# design1.net
KiCad netlist of a schematic drawn in EAGLE
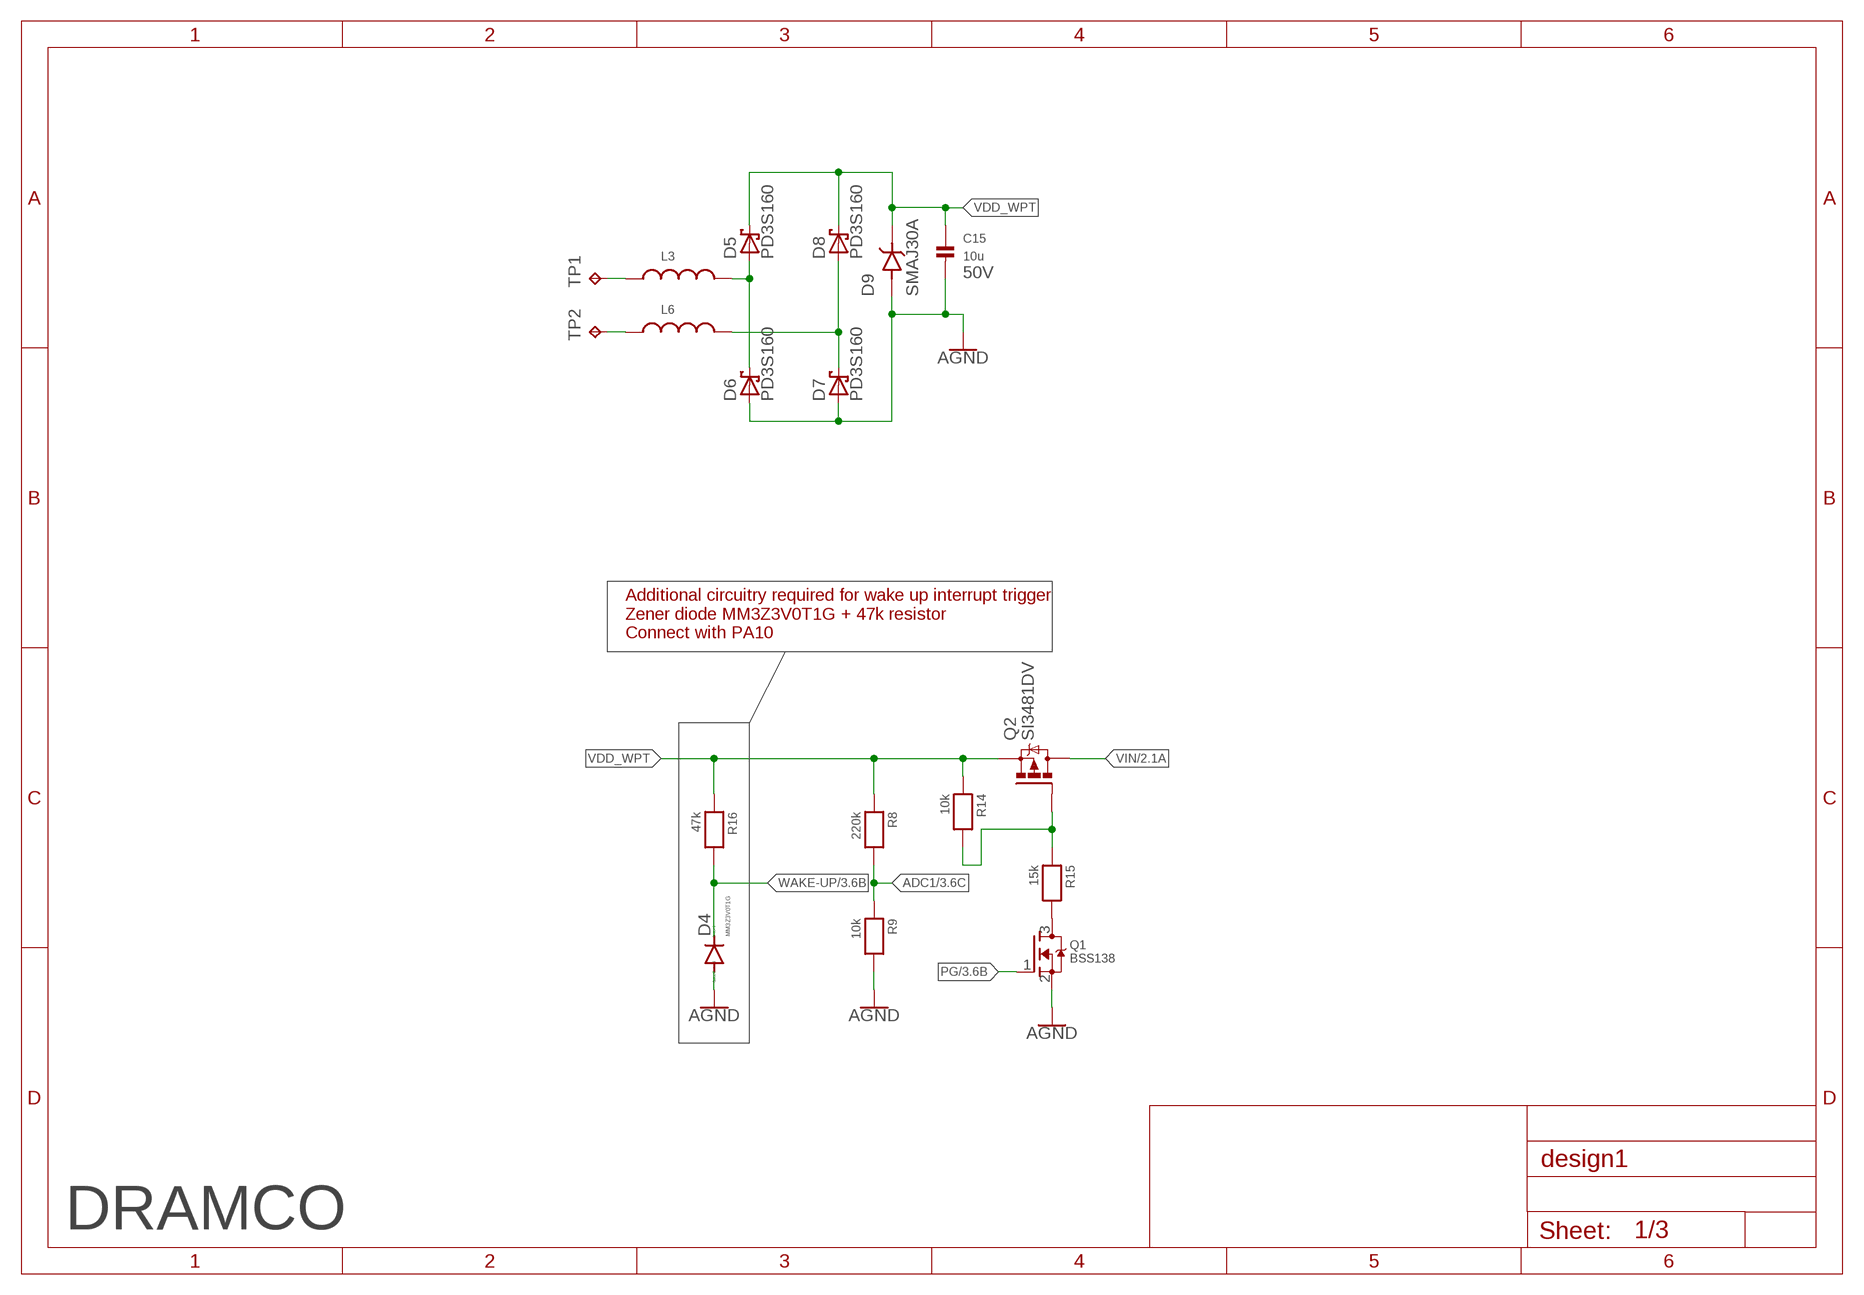
[diagram p0: schematic, sheet 1]
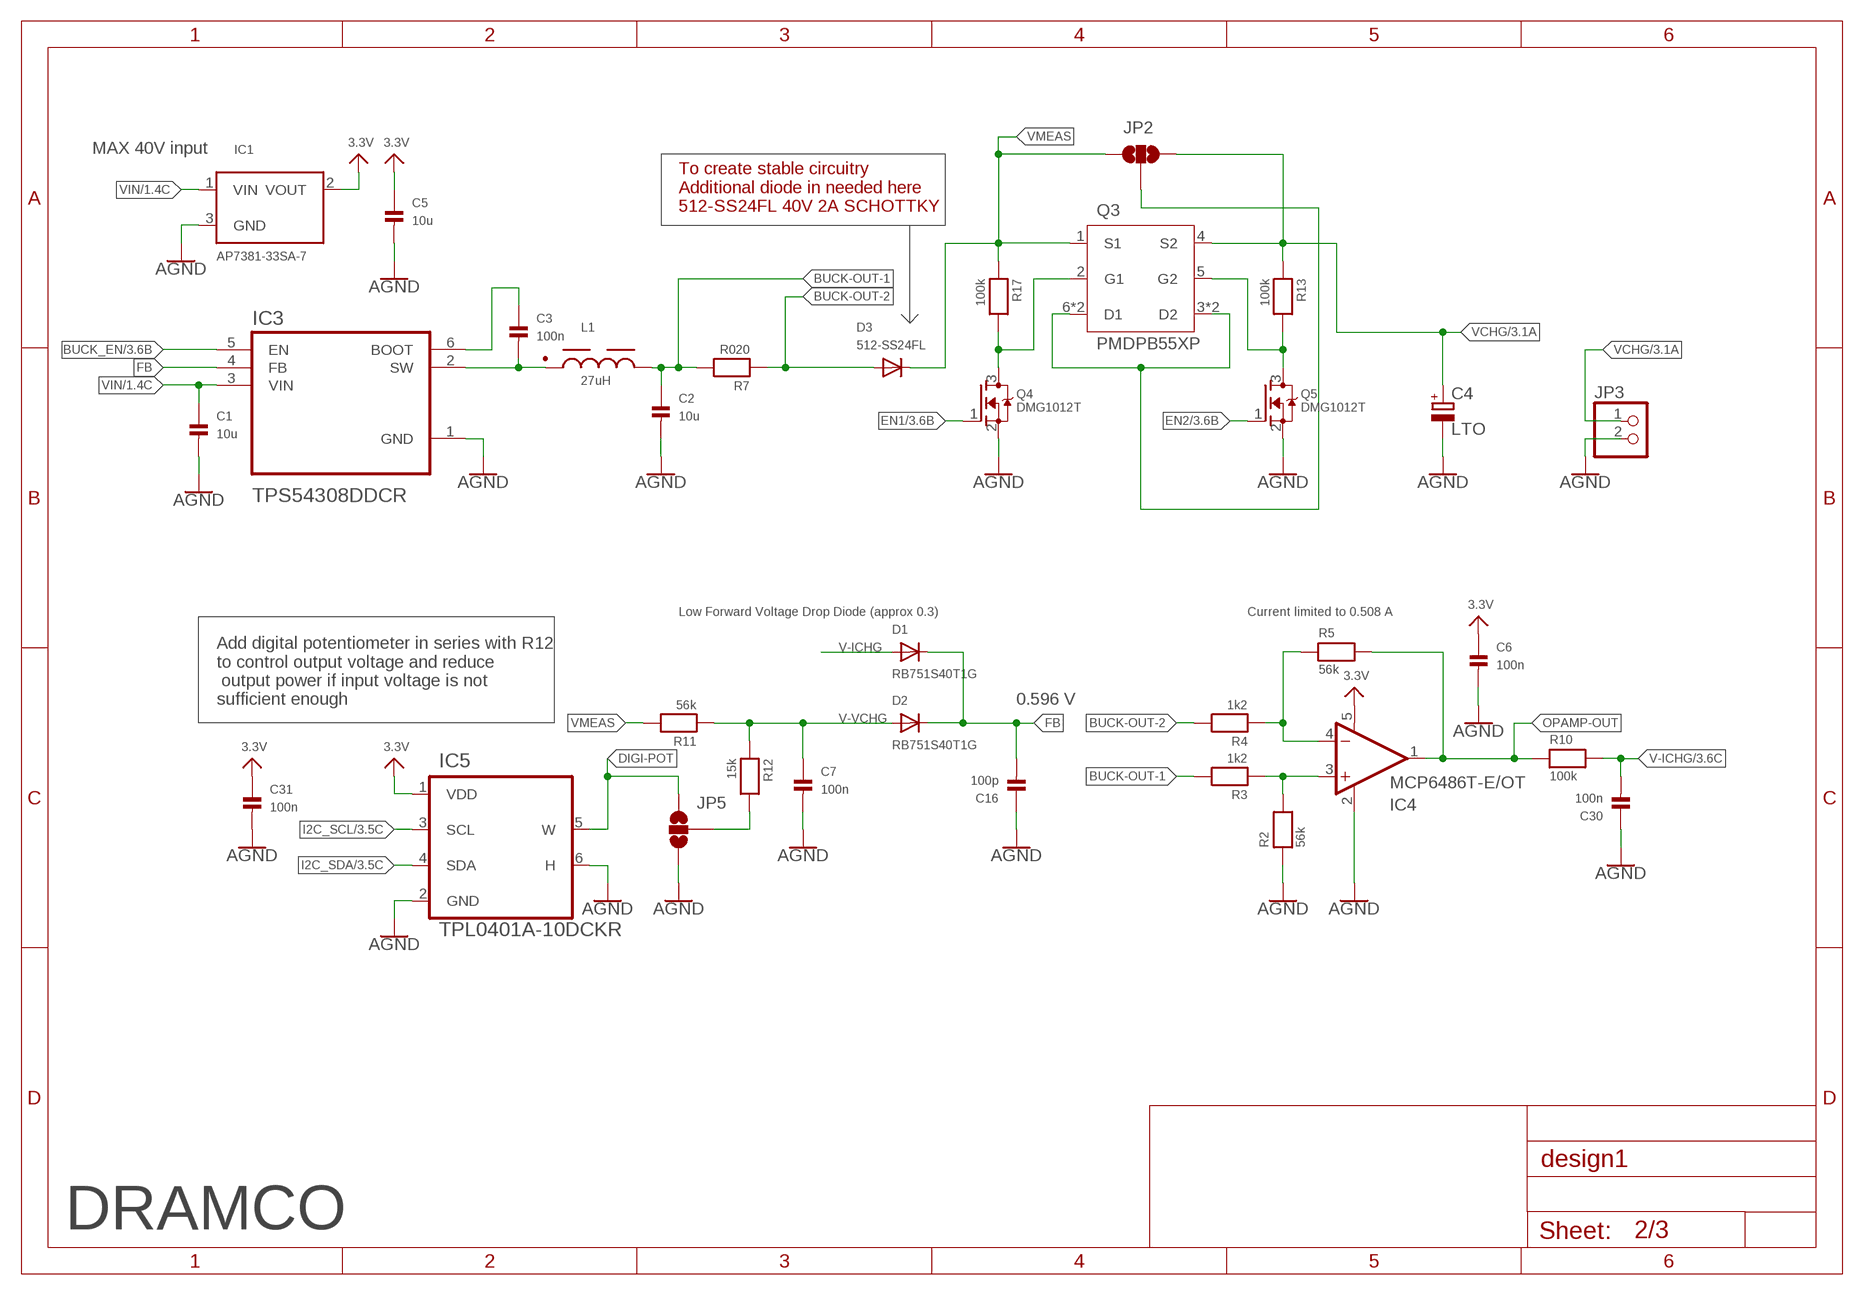
[diagram p1: schematic, sheet 2]
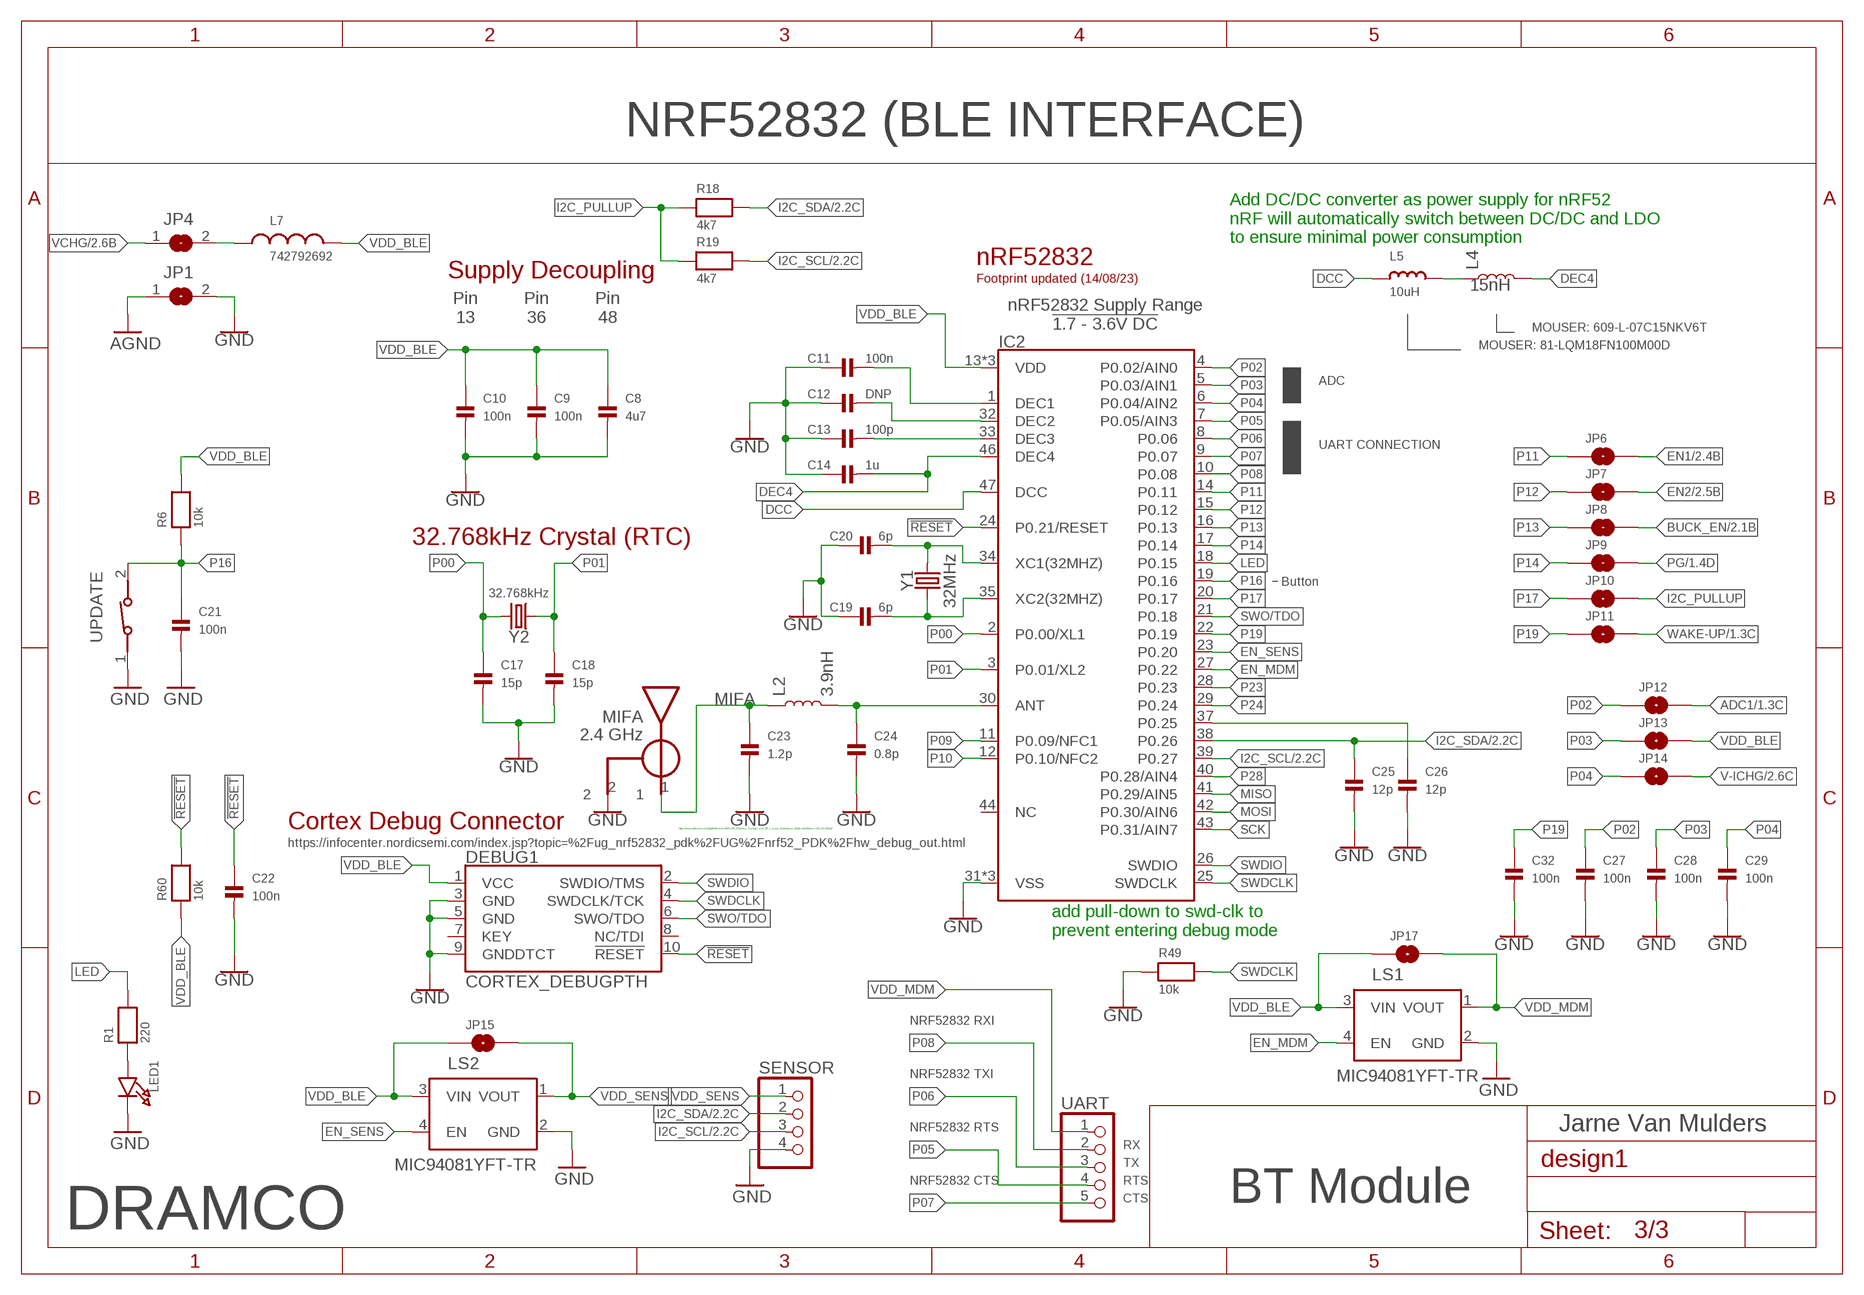
[diagram p2: schematic, sheet 3]

(export (version "E")
  (design (tool "Eeschema 10.0.6"))
  (components
    (comp (ref "C1")
      (value "10u")
      (footprint "eagle-import:0603")
      (libsource (lib "eagle-import") (part "CAP_CERAMIC0603"))
    )
    (comp (ref "C2")
      (value "10u")
      (footprint "eagle-import:0603")
      (libsource (lib "eagle-import") (part "CAP_CERAMIC0603"))
    )
    (comp (ref "C3")
      (value "100n")
      (footprint "eagle-import:0603")
      (libsource (lib "eagle-import") (part "CAP_CERAMIC0603"))
    )
    (comp (ref "C4")
      (value "LTO")
      (footprint "eagle-import:E5-10,5")
      (libsource (lib "eagle-import") (part "CPOL-EUE5-10.5"))
    )
    (comp (ref "C5")
      (value "10u")
      (footprint "eagle-import:0603")
      (libsource (lib "eagle-import") (part "CAP_CERAMIC0603"))
    )
    (comp (ref "C6")
      (value "100n")
      (footprint "eagle-import:0402")
      (libsource (lib "eagle-import") (part "CAP_CERAMIC0402"))
    )
    (comp (ref "C7")
      (value "100n")
      (footprint "eagle-import:0603")
      (libsource (lib "eagle-import") (part "CAP_CERAMIC0603"))
    )
    (comp (ref "C16")
      (value "100p")
      (footprint "eagle-import:0603")
      (libsource (lib "eagle-import") (part "CAP_CERAMIC0603"))
    )
    (comp (ref "C30")
      (value "100n")
      (footprint "eagle-import:0603")
      (libsource (lib "eagle-import") (part "CAP_CERAMIC0603"))
    )
    (comp (ref "C31")
      (value "100n")
      (footprint "eagle-import:0402")
      (libsource (lib "eagle-import") (part "CAP_CERAMIC0402"))
    )
    (comp (ref "D1")
      (value "RB751S40T1G")
      (footprint "eagle-import:SOD-523")
      (libsource (lib "eagle-import") (part "DIODESOD-523"))
    )
    (comp (ref "D2")
      (value "RB751S40T1G")
      (footprint "eagle-import:SOD-523")
      (libsource (lib "eagle-import") (part "DIODESOD-523"))
    )
    (comp (ref "D3")
      (value "512-SS24FL")
      (footprint "eagle-import:SOD-123")
      (libsource (lib "eagle-import") (part "DIODESOD-123"))
    )
    (comp (ref "IC1")
      (value "AP7381-33SA-7")
      (footprint "eagle-import:SOT23-R")
      (libsource (lib "eagle-import") (part "VREG_SOT23"))
    )
    (comp (ref "IC3")
      (value "TPS54308DDCR")
      (footprint "eagle-import:SOT95P280X110-6N")
      (fields (field (name "MF") "Texas Instruments"))
      (libsource (lib "eagle-import") (part "TPS54308DDCR"))
    )
    (comp (ref "IC4")
      (value "MCP6486T-E/OT")
      (footprint "eagle-import:SOT23-5")
      (libsource (lib "eagle-import") (part "MCP6291T-E/OT"))
    )
    (comp (ref "IC5")
      (value "TPL0401A-10DCKR")
      (footprint "eagle-import:SOT65P210X110-6N")
      (fields (field (name "MF") "Texas Instruments"))
      (libsource (lib "eagle-import") (part "TPL0401A-10DCKR"))
    )
    (comp (ref "JP2")
      (value "JUMPER-SMT_3_NO_NO-SILK")
      (footprint "eagle-import:SMT-JUMPER_3_NO_NO-SILK")
      (libsource (lib "eagle-import") (part "JUMPER-SMT_3_NO_NO-SILK"))
    )
    (comp (ref "JP3")
      (value "HEADER-1X2ROUND")
      (footprint "eagle-import:1X02_ROUND")
      (libsource (lib "eagle-import") (part "HEADER-1X2ROUND"))
    )
    (comp (ref "JP5")
      (value "JUMPER-SMT_3_NO_NO-SILK")
      (footprint "eagle-import:SMT-JUMPER_3_NO_NO-SILK")
      (libsource (lib "eagle-import") (part "JUMPER-SMT_3_NO_NO-SILK"))
    )
    (comp (ref "L1")
      (value "27uH")
      (footprint "eagle-import:WE-PD_7332_7345_PLASTIC_BASE")
      (libsource (lib "eagle-import") (part "WE-PD_7332_PLASTIC_7447789127"))
    )
    (comp (ref "Q3")
      (value "PMDPB55XP")
      (footprint "eagle-import:SON65P200X200X65-8N")
      (libsource (lib "eagle-import") (part "PMDPB55XP"))
    )
    (comp (ref "Q4")
      (value "DMG1012T")
      (footprint "eagle-import:SOT523-3")
      (libsource (lib "eagle-import") (part "DMG1012T"))
    )
    (comp (ref "Q5")
      (value "DMG1012T")
      (footprint "eagle-import:SOT523-3")
      (libsource (lib "eagle-import") (part "DMG1012T"))
    )
    (comp (ref "R2")
      (value "56k")
      (footprint "eagle-import:0603")
      (libsource (lib "eagle-import") (part "RESISTOR0603"))
    )
    (comp (ref "R3")
      (value "1k2")
      (footprint "eagle-import:0603")
      (libsource (lib "eagle-import") (part "RESISTOR0603"))
    )
    (comp (ref "R4")
      (value "1k2")
      (footprint "eagle-import:0603")
      (libsource (lib "eagle-import") (part "RESISTOR0603"))
    )
    (comp (ref "R5")
      (value "56k")
      (footprint "eagle-import:0603")
      (libsource (lib "eagle-import") (part "RESISTOR0603"))
    )
    (comp (ref "R7")
      (value "R020")
      (footprint "eagle-import:0603")
      (libsource (lib "eagle-import") (part "RESISTOR0603"))
    )
    (comp (ref "R10")
      (value "100k")
      (footprint "eagle-import:0603")
      (libsource (lib "eagle-import") (part "RESISTOR0603"))
    )
    (comp (ref "R11")
      (value "56k")
      (footprint "eagle-import:0603")
      (libsource (lib "eagle-import") (part "RESISTOR0603"))
    )
    (comp (ref "R12")
      (value "15k")
      (footprint "eagle-import:0603")
      (libsource (lib "eagle-import") (part "RESISTOR0603"))
    )
    (comp (ref "R13")
      (value "100k")
      (footprint "eagle-import:0402")
      (libsource (lib "eagle-import") (part "RESISTOR0402"))
    )
    (comp (ref "R17")
      (value "100k")
      (footprint "eagle-import:0402")
      (libsource (lib "eagle-import") (part "RESISTOR0402"))
    )
    (comp (ref "C15")
      (value "10u")
      (footprint "eagle-import:1206")
      (libsource (lib "eagle-import") (part "CAP_CERAMIC1206"))
    )
    (comp (ref "D4")
      (value "MM3Z3V0T1G")
      (footprint "eagle-import:SOD323-R")
      (libsource (lib "eagle-import") (part "DIODE-SOD323-R"))
    )
    (comp (ref "D5")
      (value "PD3S160")
      (footprint "eagle-import:POWERDI323")
      (libsource (lib "eagle-import") (part "PD3S160"))
    )
    (comp (ref "D6")
      (value "PD3S160")
      (footprint "eagle-import:POWERDI323")
      (libsource (lib "eagle-import") (part "PD3S160"))
    )
    (comp (ref "D7")
      (value "PD3S160")
      (footprint "eagle-import:POWERDI323")
      (libsource (lib "eagle-import") (part "PD3S160"))
    )
    (comp (ref "D8")
      (value "PD3S160")
      (footprint "eagle-import:POWERDI323")
      (libsource (lib "eagle-import") (part "PD3S160"))
    )
    (comp (ref "D9")
      (value "SMAJ30A")
      (footprint "eagle-import:DIOM5026X229N")
      (fields (field (name "MF") "Littelfuse"))
      (libsource (lib "eagle-import") (part "SMAJ30A"))
    )
    (comp (ref "L3")
      (value "WE-CAIR_4248_744912182")
      (footprint "eagle-import:WE-CAIR_4248")
      (libsource (lib "eagle-import") (part "WE-CAIR_4248_744912182"))
    )
    (comp (ref "L6")
      (value "WE-CAIR_4248_744912182")
      (footprint "eagle-import:WE-CAIR_4248")
      (libsource (lib "eagle-import") (part "WE-CAIR_4248_744912182"))
    )
    (comp (ref "Q1")
      (value "BSS138")
      (footprint "eagle-import:SOT23-R")
      (libsource (lib "eagle-import") (part "MOSFET-NREFLOW"))
    )
    (comp (ref "Q2")
      (value "SI3481DV")
      (footprint "eagle-import:TSOP-6.PAC")
      (libsource (lib "eagle-import") (part "SI3481DV"))
    )
    (comp (ref "R8")
      (value "220k")
      (footprint "eagle-import:0603")
      (libsource (lib "eagle-import") (part "RESISTOR0603"))
    )
    (comp (ref "R9")
      (value "10k")
      (footprint "eagle-import:0603")
      (libsource (lib "eagle-import") (part "RESISTOR0603"))
    )
    (comp (ref "R14")
      (value "10k")
      (footprint "eagle-import:0603")
      (libsource (lib "eagle-import") (part "RESISTOR0603"))
    )
    (comp (ref "R15")
      (value "15k")
      (footprint "eagle-import:0603")
      (libsource (lib "eagle-import") (part "RESISTOR0603"))
    )
    (comp (ref "R16")
      (value "47k")
      (footprint "eagle-import:0603")
      (libsource (lib "eagle-import") (part "RESISTOR0603"))
    )
    (comp (ref "TP1")
      (value "TPTP20SQ")
      (footprint "eagle-import:TP20SQ")
      (libsource (lib "eagle-import") (part "TPTP20SQ"))
    )
    (comp (ref "TP2")
      (value "TPTP20SQ")
      (footprint "eagle-import:TP20SQ")
      (libsource (lib "eagle-import") (part "TPTP20SQ"))
    )
    (comp (ref "C8")
      (value "4u7")
      (footprint "eagle-import:0603")
      (libsource (lib "eagle-import") (part "CAP_CERAMIC0603"))
    )
    (comp (ref "C9")
      (value "100n")
      (footprint "eagle-import:0402")
      (libsource (lib "eagle-import") (part "CAP_CERAMIC0402"))
    )
    (comp (ref "C10")
      (value "100n")
      (footprint "eagle-import:0402")
      (libsource (lib "eagle-import") (part "CAP_CERAMIC0402"))
    )
    (comp (ref "C11")
      (value "100n")
      (footprint "eagle-import:0402")
      (libsource (lib "eagle-import") (part "CAP_CERAMIC0402"))
    )
    (comp (ref "C12")
      (value "DNP")
      (footprint "eagle-import:0402")
      (libsource (lib "eagle-import") (part "CAP_CERAMIC0402"))
    )
    (comp (ref "C13")
      (value "100p")
      (footprint "eagle-import:0402")
      (libsource (lib "eagle-import") (part "CAP_CERAMIC0402"))
    )
    (comp (ref "C14")
      (value "1u")
      (footprint "eagle-import:0402")
      (libsource (lib "eagle-import") (part "CAP_CERAMIC0402"))
    )
    (comp (ref "C17")
      (value "15p")
      (footprint "eagle-import:0402")
      (libsource (lib "eagle-import") (part "CAP_CERAMIC0402"))
    )
    (comp (ref "C18")
      (value "15p")
      (footprint "eagle-import:0402")
      (libsource (lib "eagle-import") (part "CAP_CERAMIC0402"))
    )
    (comp (ref "C19")
      (value "6p")
      (footprint "eagle-import:0402")
      (libsource (lib "eagle-import") (part "CAP_CERAMIC0402"))
    )
    (comp (ref "C20")
      (value "6p")
      (footprint "eagle-import:0402")
      (libsource (lib "eagle-import") (part "CAP_CERAMIC0402"))
    )
    (comp (ref "C21")
      (value "100n")
      (footprint "eagle-import:0402")
      (libsource (lib "eagle-import") (part "CAP_CERAMIC0402"))
    )
    (comp (ref "C22")
      (value "100n")
      (footprint "eagle-import:0402")
      (libsource (lib "eagle-import") (part "CAP_CERAMIC0402"))
    )
    (comp (ref "C23")
      (value "1.2p")
      (footprint "eagle-import:0402")
      (libsource (lib "eagle-import") (part "CAP_CERAMIC0402"))
    )
    (comp (ref "C24")
      (value "0.8p")
      (footprint "eagle-import:0402")
      (libsource (lib "eagle-import") (part "CAP_CERAMIC0402"))
    )
    (comp (ref "C25")
      (value "12p")
      (footprint "eagle-import:0402")
      (libsource (lib "eagle-import") (part "CAP_CERAMIC0402"))
    )
    (comp (ref "C26")
      (value "12p")
      (footprint "eagle-import:0402")
      (libsource (lib "eagle-import") (part "CAP_CERAMIC0402"))
    )
    (comp (ref "C27")
      (value "100n")
      (footprint "eagle-import:0402")
      (libsource (lib "eagle-import") (part "CAP_CERAMIC0402"))
    )
    (comp (ref "C28")
      (value "100n")
      (footprint "eagle-import:0402")
      (libsource (lib "eagle-import") (part "CAP_CERAMIC0402"))
    )
    (comp (ref "C29")
      (value "100n")
      (footprint "eagle-import:0402")
      (libsource (lib "eagle-import") (part "CAP_CERAMIC0402"))
    )
    (comp (ref "C32")
      (value "100n")
      (footprint "eagle-import:0402")
      (libsource (lib "eagle-import") (part "CAP_CERAMIC0402"))
    )
    (comp (ref "DEBUG1")
      (value "CORTEX_DEBUGPTH")
      (footprint "eagle-import:2X5-PTH-1.27MM")
      (libsource (lib "eagle-import") (part "CORTEX_DEBUGPTH"))
    )
    (comp (ref "IC2")
      (value "NRF52832-EXTENDED")
      (footprint "eagle-import:QFN48-6X6MM-EXTENDED")
      (libsource (lib "eagle-import") (part "NRF52832-EXTENDED"))
    )
    (comp (ref "JP1")
      (value "SOLDERJUMPERREFLOW_NOPASTE")
      (footprint "eagle-import:SOLDERJUMPER_REFLOW_NOPASTE")
      (libsource (lib "eagle-import") (part "SOLDERJUMPERREFLOW_NOPASTE"))
    )
    (comp (ref "JP4")
      (value "SOLDERJUMPERREFLOW_NOPASTE")
      (footprint "eagle-import:SOLDERJUMPER_REFLOW_NOPASTE")
      (libsource (lib "eagle-import") (part "SOLDERJUMPERREFLOW_NOPASTE"))
    )
    (comp (ref "JP6")
      (value "JUMPER-SMT_2_NO_NO-SILK")
      (footprint "eagle-import:SMT-JUMPER_2_NO_NO-SILK")
      (libsource (lib "eagle-import") (part "JUMPER-SMT_2_NO_NO-SILK"))
    )
    (comp (ref "JP7")
      (value "JUMPER-SMT_2_NO_NO-SILK")
      (footprint "eagle-import:SMT-JUMPER_2_NO_NO-SILK")
      (libsource (lib "eagle-import") (part "JUMPER-SMT_2_NO_NO-SILK"))
    )
    (comp (ref "JP8")
      (value "JUMPER-SMT_2_NO_NO-SILK")
      (footprint "eagle-import:SMT-JUMPER_2_NO_NO-SILK")
      (libsource (lib "eagle-import") (part "JUMPER-SMT_2_NO_NO-SILK"))
    )
    (comp (ref "JP9")
      (value "JUMPER-SMT_2_NO_NO-SILK")
      (footprint "eagle-import:SMT-JUMPER_2_NO_NO-SILK")
      (libsource (lib "eagle-import") (part "JUMPER-SMT_2_NO_NO-SILK"))
    )
    (comp (ref "JP10")
      (value "JUMPER-SMT_2_NO_NO-SILK")
      (footprint "eagle-import:SMT-JUMPER_2_NO_NO-SILK")
      (libsource (lib "eagle-import") (part "JUMPER-SMT_2_NO_NO-SILK"))
    )
    (comp (ref "JP11")
      (value "JUMPER-SMT_2_NO_NO-SILK")
      (footprint "eagle-import:SMT-JUMPER_2_NO_NO-SILK")
      (libsource (lib "eagle-import") (part "JUMPER-SMT_2_NO_NO-SILK"))
    )
    (comp (ref "JP12")
      (value "JUMPER-SMT_2_NO_NO-SILK")
      (footprint "eagle-import:SMT-JUMPER_2_NO_NO-SILK")
      (libsource (lib "eagle-import") (part "JUMPER-SMT_2_NO_NO-SILK"))
    )
    (comp (ref "JP13")
      (value "JUMPER-SMT_2_NO_NO-SILK")
      (footprint "eagle-import:SMT-JUMPER_2_NO_NO-SILK")
      (libsource (lib "eagle-import") (part "JUMPER-SMT_2_NO_NO-SILK"))
    )
    (comp (ref "JP14")
      (value "JUMPER-SMT_2_NO_NO-SILK")
      (footprint "eagle-import:SMT-JUMPER_2_NO_NO-SILK")
      (libsource (lib "eagle-import") (part "JUMPER-SMT_2_NO_NO-SILK"))
    )
    (comp (ref "JP15")
      (value "JUMPER-SMT_2_NO_NO-SILK")
      (footprint "eagle-import:SMT-JUMPER_2_NO_NO-SILK")
      (libsource (lib "eagle-import") (part "JUMPER-SMT_2_NO_NO-SILK"))
    )
    (comp (ref "JP17")
      (value "JUMPER-SMT_2_NO_NO-SILK")
      (footprint "eagle-import:SMT-JUMPER_2_NO_NO-SILK")
      (libsource (lib "eagle-import") (part "JUMPER-SMT_2_NO_NO-SILK"))
    )
    (comp (ref "L2")
      (value "3.9nH")
      (footprint "eagle-import:0402")
      (libsource (lib "eagle-import") (part "INDUCTOR-0402-3.9NH"))
    )
    (comp (ref "L4")
      (value "15nH")
      (footprint "eagle-import:0402")
      (libsource (lib "eagle-import") (part "INDUCTOR-0402-3.9NH"))
    )
    (comp (ref "L5")
      (value "10uH")
      (footprint "eagle-import:_0603MP")
      (libsource (lib "eagle-import") (part "INDUCTOR_0603MP"))
    )
    (comp (ref "L7")
      (value "742792692")
      (footprint "eagle-import:WE-CBF_0603(W=2.2)")
      (libsource (lib "eagle-import") (part "WE-CBF_0603_WB_HS_742792692"))
    )
    (comp (ref "LED1")
      (value "LED0805")
      (footprint "eagle-import:CHIPLED_0805")
      (libsource (lib "eagle-import") (part "LED0805"))
    )
    (comp (ref "LS1")
      (value "MIC94081YFT-TR")
      (footprint "eagle-import:IC_MIC94081YFT-TR")
      (fields (field (name "MF") "Microchip"))
      (libsource (lib "eagle-import") (part "MIC94081YFT-TR"))
    )
    (comp (ref "LS2")
      (value "MIC94081YFT-TR")
      (footprint "eagle-import:IC_MIC94081YFT-TR")
      (fields (field (name "MF") "Microchip"))
      (libsource (lib "eagle-import") (part "MIC94081YFT-TR"))
    )
    (comp (ref "R1")
      (value "220")
      (footprint "eagle-import:0603")
      (libsource (lib "eagle-import") (part "RESISTOR0603"))
    )
    (comp (ref "R6")
      (value "10k")
      (footprint "eagle-import:0402")
      (libsource (lib "eagle-import") (part "RESISTOR0402"))
    )
    (comp (ref "R18")
      (value "4k7")
      (footprint "eagle-import:0402")
      (libsource (lib "eagle-import") (part "RESISTOR0402"))
    )
    (comp (ref "R19")
      (value "4k7")
      (footprint "eagle-import:0402")
      (libsource (lib "eagle-import") (part "RESISTOR0402"))
    )
    (comp (ref "R49")
      (value "10k")
      (footprint "eagle-import:0402")
      (libsource (lib "eagle-import") (part "RESISTOR0402"))
    )
    (comp (ref "R60")
      (value "10k")
      (footprint "eagle-import:0402")
      (libsource (lib "eagle-import") (part "RESISTOR0402"))
    )
    (comp (ref "SENSOR")
      (value "HEADER-1X4ROUND")
      (footprint "eagle-import:1X04_ROUND")
      (libsource (lib "eagle-import") (part "HEADER-1X4ROUND"))
    )
    (comp (ref "U$18")
      (value "BLE-ANT")
      (footprint "eagle-import:ANT-2G4")
      (libsource (lib "eagle-import") (part "BLE-ANT"))
    )
    (comp (ref "UART")
      (value "HEADER-1X5ROUND")
      (footprint "eagle-import:1X05_ROUND")
      (libsource (lib "eagle-import") (part "HEADER-1X5ROUND"))
    )
    (comp (ref "UPDATE")
      (value "434111043826")
      (footprint "eagle-import:434111043826")
      (libsource (lib "eagle-import") (part "434111043826"))
    )
    (comp (ref "Y1")
      (value "32MHz")
      (footprint "eagle-import:CRYSTAL-SMD-2.0X1.6MM")
      (libsource (lib "eagle-import") (part "CRYSTAL-32MHZ-SMD-2.0X1.6MM"))
    )
    (comp (ref "Y2")
      (value "32.768kHz")
      (footprint "eagle-import:CRYSTAL-SMD-3.2X1.5MM")
      (libsource (lib "eagle-import") (part "CRYSTAL-32.768KHZSMD-3.2X1.5"))
    )
  )
  (nets
    (net (code "1") (name "3.3V") (class "Default")
      (node (ref "C31") (pin "1") (pinfunction "P$1_1") (pintype "passive"))
      (node (ref "C5") (pin "1") (pinfunction "P$1_1") (pintype "passive"))
      (node (ref "C6") (pin "1") (pinfunction "P$1_1") (pintype "passive"))
      (node (ref "IC1") (pin "2") (pinfunction "VOUT_2") (pintype "power_in"))
      (node (ref "IC4") (pin "5") (pinfunction "V+_5") (pintype "power_in"))
      (node (ref "IC5") (pin "1") (pinfunction "VDD_1") (pintype "power_in"))
    )
    (net (code "2") (name "ADC1") (class "Default")
      (node (ref "JP12") (pin "2") (pinfunction "2_2") (pintype "passive"))
      (node (ref "R8") (pin "2") (pinfunction "2_2") (pintype "passive"))
      (node (ref "R9") (pin "1") (pinfunction "1_1") (pintype "passive"))
    )
    (net (code "3") (name "AGND") (class "Default")
      (node (ref "C1") (pin "2") (pinfunction "P$2_2") (pintype "passive"))
      (node (ref "C15") (pin "2") (pinfunction "P$2_2") (pintype "passive"))
      (node (ref "C16") (pin "1") (pinfunction "P$1_1") (pintype "passive"))
      (node (ref "C2") (pin "2") (pinfunction "P$2_2") (pintype "passive"))
      (node (ref "C30") (pin "1") (pinfunction "P$1_1") (pintype "passive"))
      (node (ref "C31") (pin "2") (pinfunction "P$2_2") (pintype "passive"))
      (node (ref "C4") (pin "-") (pinfunction "-_-") (pintype "passive"))
      (node (ref "C5") (pin "2") (pinfunction "P$2_2") (pintype "passive"))
      (node (ref "C6") (pin "2") (pinfunction "P$2_2") (pintype "passive"))
      (node (ref "C7") (pin "2") (pinfunction "P$2_2") (pintype "passive"))
      (node (ref "D4") (pin "A") (pinfunction "A_A") (pintype "passive"))
      (node (ref "D6") (pin "A") (pinfunction "A_A") (pintype "passive"))
      (node (ref "D7") (pin "A") (pinfunction "A_A") (pintype "passive"))
      (node (ref "D9") (pin "A") (pinfunction "A_A") (pintype "passive"))
      (node (ref "IC1") (pin "3") (pinfunction "GND_3") (pintype "power_in"))
      (node (ref "IC3") (pin "1") (pinfunction "GND_1") (pintype "power_in"))
      (node (ref "IC4") (pin "2") (pinfunction "V-_2") (pintype "power_in"))
      (node (ref "IC5") (pin "2") (pinfunction "GND_2") (pintype "power_in"))
      (node (ref "IC5") (pin "6") (pinfunction "H_6") (pintype "bidirectional"))
      (node (ref "JP1") (pin "1") (pinfunction "1_1") (pintype "passive"))
      (node (ref "JP3") (pin "2") (pinfunction "2_2") (pintype "passive"))
      (node (ref "JP5") (pin "1") (pinfunction "1_1") (pintype "passive"))
      (node (ref "Q1") (pin "2") (pinfunction "S_2") (pintype "bidirectional"))
      (node (ref "Q4") (pin "2") (pinfunction "S_2") (pintype "bidirectional"))
      (node (ref "Q5") (pin "2") (pinfunction "S_2") (pintype "bidirectional"))
      (node (ref "R2") (pin "1") (pinfunction "1_1") (pintype "passive"))
      (node (ref "R9") (pin "2") (pinfunction "2_2") (pintype "passive"))
    )
    (net (code "4") (name "BUCK-OUT-1") (class "Default")
      (node (ref "C2") (pin "1") (pinfunction "P$1_1") (pintype "passive"))
      (node (ref "L1") (pin "2") (pinfunction "2_2") (pintype "passive"))
      (node (ref "R3") (pin "2") (pinfunction "2_2") (pintype "passive"))
      (node (ref "R7") (pin "2") (pinfunction "2_2") (pintype "passive"))
    )
    (net (code "5") (name "BUCK-OUT-2") (class "Default")
      (node (ref "D3") (pin "A") (pinfunction "A_A") (pintype "passive"))
      (node (ref "R4") (pin "2") (pinfunction "2_2") (pintype "passive"))
      (node (ref "R7") (pin "1") (pinfunction "1_1") (pintype "passive"))
    )
    (net (code "6") (name "BUCK_EN") (class "Default")
      (node (ref "IC3") (pin "5") (pinfunction "EN_5") (pintype "input"))
      (node (ref "JP8") (pin "2") (pinfunction "2_2") (pintype "passive"))
    )
    (net (code "7") (name "DCC") (class "Default")
      (node (ref "IC2") (pin "47") (pinfunction "DCC_47") (pintype "bidirectional"))
      (node (ref "L5") (pin "1") (pinfunction "1_1") (pintype "passive"))
    )
    (net (code "8") (name "DEC4") (class "Default")
      (node (ref "C14") (pin "2") (pinfunction "P$2_2") (pintype "passive"))
      (node (ref "IC2") (pin "46") (pinfunction "DEC4_46") (pintype "bidirectional"))
      (node (ref "L4") (pin "2") (pinfunction "2_2") (pintype "passive"))
    )
    (net (code "9") (name "DIGI-POT") (class "Default")
      (node (ref "IC5") (pin "5") (pinfunction "W_5") (pintype "bidirectional"))
      (node (ref "JP5") (pin "3") (pinfunction "3_3") (pintype "passive"))
    )
    (net (code "10") (name "EN1") (class "Default")
      (node (ref "JP6") (pin "2") (pinfunction "2_2") (pintype "passive"))
      (node (ref "Q4") (pin "1") (pinfunction "G_1") (pintype "bidirectional"))
    )
    (net (code "11") (name "EN2") (class "Default")
      (node (ref "JP7") (pin "2") (pinfunction "2_2") (pintype "passive"))
      (node (ref "Q5") (pin "1") (pinfunction "G_1") (pintype "bidirectional"))
    )
    (net (code "12") (name "EN_MDM") (class "Default")
      (node (ref "IC2") (pin "27") (pinfunction "P0.22_27") (pintype "bidirectional"))
      (node (ref "LS1") (pin "4") (pinfunction "EN_4") (pintype "input"))
    )
    (net (code "13") (name "EN_SENS") (class "Default")
      (node (ref "IC2") (pin "23") (pinfunction "P0.20_23") (pintype "bidirectional"))
      (node (ref "LS2") (pin "4") (pinfunction "EN_4") (pintype "input"))
    )
    (net (code "14") (name "FB") (class "Default")
      (node (ref "C16") (pin "2") (pinfunction "P$2_2") (pintype "passive"))
      (node (ref "D1") (pin "K") (pinfunction "C_K") (pintype "passive"))
      (node (ref "D2") (pin "K") (pinfunction "C_K") (pintype "passive"))
      (node (ref "IC3") (pin "4") (pinfunction "FB_4") (pintype "input"))
    )
    (net (code "15") (name "GND") (class "Default")
      (node (ref "C10") (pin "2") (pinfunction "P$2_2") (pintype "passive"))
      (node (ref "C11") (pin "1") (pinfunction "P$1_1") (pintype "passive"))
      (node (ref "C12") (pin "1") (pinfunction "P$1_1") (pintype "passive"))
      (node (ref "C13") (pin "1") (pinfunction "P$1_1") (pintype "passive"))
      (node (ref "C14") (pin "1") (pinfunction "P$1_1") (pintype "passive"))
      (node (ref "C17") (pin "2") (pinfunction "P$2_2") (pintype "passive"))
      (node (ref "C18") (pin "2") (pinfunction "P$2_2") (pintype "passive"))
      (node (ref "C19") (pin "1") (pinfunction "P$1_1") (pintype "passive"))
      (node (ref "C20") (pin "1") (pinfunction "P$1_1") (pintype "passive"))
      (node (ref "C21") (pin "2") (pinfunction "P$2_2") (pintype "passive"))
      (node (ref "C22") (pin "2") (pinfunction "P$2_2") (pintype "passive"))
      (node (ref "C23") (pin "2") (pinfunction "P$2_2") (pintype "passive"))
      (node (ref "C24") (pin "2") (pinfunction "P$2_2") (pintype "passive"))
      (node (ref "C25") (pin "2") (pinfunction "P$2_2") (pintype "passive"))
      (node (ref "C26") (pin "2") (pinfunction "P$2_2") (pintype "passive"))
      (node (ref "C27") (pin "2") (pinfunction "P$2_2") (pintype "passive"))
      (node (ref "C28") (pin "2") (pinfunction "P$2_2") (pintype "passive"))
      (node (ref "C29") (pin "2") (pinfunction "P$2_2") (pintype "passive"))
      (node (ref "C32") (pin "2") (pinfunction "P$2_2") (pintype "passive"))
      (node (ref "C8") (pin "2") (pinfunction "P$2_2") (pintype "passive"))
      (node (ref "C9") (pin "2") (pinfunction "P$2_2") (pintype "passive"))
      (node (ref "DEBUG1") (pin "3") (pinfunction "GND_3") (pintype "bidirectional"))
      (node (ref "DEBUG1") (pin "5") (pinfunction "GND_5") (pintype "bidirectional"))
      (node (ref "DEBUG1") (pin "9") (pinfunction "GNDDTCT_9") (pintype "bidirectional"))
      (node (ref "IC2") (pin "31") (pinfunction "VSS_31") (pintype "bidirectional"))
      (node (ref "IC2") (pin "45") (pinfunction "VSS_45") (pintype "bidirectional"))
      (node (ref "IC2") (pin "EP") (pinfunction "VSS_EP") (pintype "bidirectional"))
      (node (ref "JP1") (pin "2") (pinfunction "2_2") (pintype "passive"))
      (node (ref "LED1") (pin "C") (pinfunction "C_C") (pintype "passive"))
      (node (ref "LS1") (pin "2") (pinfunction "GND_2") (pintype "power_in"))
      (node (ref "LS2") (pin "2") (pinfunction "GND_2") (pintype "power_in"))
      (node (ref "R49") (pin "1") (pinfunction "1_1") (pintype "passive"))
      (node (ref "SENSOR") (pin "4") (pinfunction "4_4") (pintype "passive"))
      (node (ref "U$18") (pin "2") (pinfunction "2_2") (pintype "bidirectional"))
      (node (ref "UPDATE") (pin "1") (pinfunction "1_1") (pintype "passive"))
    )
    (net (code "16") (name "I2C_PULLUP") (class "Default")
      (node (ref "JP10") (pin "2") (pinfunction "2_2") (pintype "passive"))
      (node (ref "R18") (pin "1") (pinfunction "1_1") (pintype "passive"))
      (node (ref "R19") (pin "1") (pinfunction "1_1") (pintype "passive"))
    )
    (net (code "17") (name "I2C_SCL") (class "Default")
      (node (ref "IC2") (pin "39") (pinfunction "P0.27_39") (pintype "bidirectional"))
      (node (ref "IC5") (pin "3") (pinfunction "SCL_3") (pintype "bidirectional"))
      (node (ref "R19") (pin "2") (pinfunction "2_2") (pintype "passive"))
      (node (ref "SENSOR") (pin "3") (pinfunction "3_3") (pintype "passive"))
    )
    (net (code "18") (name "I2C_SDA") (class "Default")
      (node (ref "C25") (pin "1") (pinfunction "P$1_1") (pintype "passive"))
      (node (ref "IC2") (pin "38") (pinfunction "P0.26_38") (pintype "bidirectional"))
      (node (ref "IC5") (pin "4") (pinfunction "SDA_4") (pintype "bidirectional"))
      (node (ref "R18") (pin "2") (pinfunction "2_2") (pintype "passive"))
      (node (ref "SENSOR") (pin "2") (pinfunction "2_2") (pintype "passive"))
    )
    (net (code "19") (name "LED") (class "Default")
      (node (ref "IC2") (pin "18") (pinfunction "P0.15_18") (pintype "bidirectional"))
      (node (ref "R1") (pin "2") (pinfunction "2_2") (pintype "passive"))
    )
    (net (code "20") (name "MIFA") (class "Default")
      (node (ref "C23") (pin "1") (pinfunction "P$1_1") (pintype "passive"))
      (node (ref "L2") (pin "1") (pinfunction "1_1") (pintype "passive"))
      (node (ref "U$18") (pin "1") (pinfunction "1_1") (pintype "bidirectional"))
    )
    (net (code "21") (name "MISO") (class "Default")
      (node (ref "IC2") (pin "41") (pinfunction "P0.29/AIN5_41") (pintype "bidirectional"))
    )
    (net (code "22") (name "MOSI") (class "Default")
      (node (ref "IC2") (pin "42") (pinfunction "P0.30/AIN6_42") (pintype "bidirectional"))
    )
    (net (code "23") (name "Net-(C3-P$1)") (class "Default")
      (node (ref "C3") (pin "1") (pinfunction "P$1_1") (pintype "passive"))
      (node (ref "IC3") (pin "6") (pinfunction "BOOT_6") (pintype "output"))
    )
    (net (code "24") (name "Net-(C3-P$2)") (class "Default")
      (node (ref "C3") (pin "2") (pinfunction "P$2_2") (pintype "passive"))
      (node (ref "IC3") (pin "2") (pinfunction "SW_2") (pintype "output"))
      (node (ref "L1") (pin "1") (pinfunction "1_1") (pintype "passive"))
    )
    (net (code "25") (name "Net-(C11-P$2)") (class "Default")
      (node (ref "C11") (pin "2") (pinfunction "P$2_2") (pintype "passive"))
      (node (ref "IC2") (pin "1") (pinfunction "DEC1_1") (pintype "bidirectional"))
    )
    (net (code "26") (name "Net-(C12-P$2)") (class "Default")
      (node (ref "C12") (pin "2") (pinfunction "P$2_2") (pintype "passive"))
      (node (ref "IC2") (pin "32") (pinfunction "DEC2_32") (pintype "bidirectional"))
    )
    (net (code "27") (name "Net-(C13-P$2)") (class "Default")
      (node (ref "C13") (pin "2") (pinfunction "P$2_2") (pintype "passive"))
      (node (ref "IC2") (pin "33") (pinfunction "DEC3_33") (pintype "bidirectional"))
    )
    (net (code "28") (name "Net-(C19-P$2)") (class "Default")
      (node (ref "C19") (pin "2") (pinfunction "P$2_2") (pintype "passive"))
      (node (ref "IC2") (pin "35") (pinfunction "XC2(32MHZ)_35") (pintype "bidirectional"))
      (node (ref "Y1") (pin "1") (pinfunction "1_1") (pintype "passive"))
    )
    (net (code "29") (name "Net-(C20-P$2)") (class "Default")
      (node (ref "C20") (pin "2") (pinfunction "P$2_2") (pintype "passive"))
      (node (ref "IC2") (pin "34") (pinfunction "XC1(32MHZ)_34") (pintype "bidirectional"))
      (node (ref "Y1") (pin "3") (pinfunction "2_3") (pintype "passive"))
    )
    (net (code "30") (name "Net-(C24-P$1)") (class "Default")
      (node (ref "C24") (pin "1") (pinfunction "P$1_1") (pintype "passive"))
      (node (ref "IC2") (pin "30") (pinfunction "ANT_30") (pintype "bidirectional"))
      (node (ref "L2") (pin "2") (pinfunction "2_2") (pintype "passive"))
    )
    (net (code "31") (name "Net-(C26-P$1)") (class "Default")
      (node (ref "C26") (pin "1") (pinfunction "P$1_1") (pintype "passive"))
      (node (ref "IC2") (pin "37") (pinfunction "P0.25_37") (pintype "bidirectional"))
    )
    (net (code "32") (name "Net-(D5-PadA)") (class "Default")
      (node (ref "D5") (pin "A") (pinfunction "A_A") (pintype "passive"))
      (node (ref "D6") (pin "C") (pinfunction "C_C") (pintype "passive"))
      (node (ref "L3") (pin "2") (pinfunction "2_2") (pintype "passive"))
    )
    (net (code "33") (name "Net-(D7-PadC)") (class "Default")
      (node (ref "D7") (pin "C") (pinfunction "C_C") (pintype "passive"))
      (node (ref "D8") (pin "A") (pinfunction "A_A") (pintype "passive"))
      (node (ref "L6") (pin "2") (pinfunction "2_2") (pintype "passive"))
    )
    (net (code "34") (name "Net-(IC4-+IN)") (class "Default")
      (node (ref "IC4") (pin "3") (pinfunction "+IN_3") (pintype "input"))
      (node (ref "R2") (pin "2") (pinfunction "2_2") (pintype "passive"))
      (node (ref "R3") (pin "1") (pinfunction "1_1") (pintype "passive"))
    )
    (net (code "35") (name "Net-(IC4--IN)") (class "Default")
      (node (ref "IC4") (pin "4") (pinfunction "-IN_4") (pintype "input"))
      (node (ref "R4") (pin "1") (pinfunction "1_1") (pintype "passive"))
      (node (ref "R5") (pin "1") (pinfunction "1_1") (pintype "passive"))
    )
    (net (code "36") (name "Net-(JP2-Pad2)") (class "Default")
      (node (ref "JP2") (pin "2") (pinfunction "2_2") (pintype "passive"))
      (node (ref "Q3") (pin "3") (pinfunction "D2_3") (pintype "bidirectional"))
      (node (ref "Q3") (pin "6") (pinfunction "D1_6") (pintype "bidirectional"))
      (node (ref "Q3") (pin "7") (pinfunction "D1_7") (pintype "bidirectional"))
      (node (ref "Q3") (pin "8") (pinfunction "D2_8") (pintype "bidirectional"))
    )
    (net (code "37") (name "Net-(JP4-Pad2)") (class "Default")
      (node (ref "JP4") (pin "2") (pinfunction "2_2") (pintype "passive"))
      (node (ref "L7") (pin "1") (pinfunction "1_1") (pintype "passive"))
    )
    (net (code "38") (name "Net-(JP5-Pad2)") (class "Default")
      (node (ref "JP5") (pin "2") (pinfunction "2_2") (pintype "passive"))
      (node (ref "R12") (pin "2") (pinfunction "2_2") (pintype "passive"))
    )
    (net (code "39") (name "Net-(L3-Pad1)") (class "Default")
      (node (ref "L3") (pin "1") (pinfunction "1_1") (pintype "passive"))
      (node (ref "TP1") (pin "TP") (pinfunction "TP_TP") (pintype "input"))
    )
    (net (code "40") (name "Net-(L4-Pad1)") (class "Default")
      (node (ref "L4") (pin "1") (pinfunction "1_1") (pintype "passive"))
      (node (ref "L5") (pin "2") (pinfunction "2_2") (pintype "passive"))
    )
    (net (code "41") (name "Net-(L6-Pad1)") (class "Default")
      (node (ref "L6") (pin "1") (pinfunction "1_1") (pintype "passive"))
      (node (ref "TP2") (pin "TP") (pinfunction "TP_TP") (pintype "input"))
    )
    (net (code "42") (name "Net-(LED1-PadA)") (class "Default")
      (node (ref "LED1") (pin "A") (pinfunction "A_A") (pintype "passive"))
      (node (ref "R1") (pin "1") (pinfunction "1_1") (pintype "passive"))
    )
    (net (code "43") (name "Net-(Q1-D)") (class "Default")
      (node (ref "Q1") (pin "3") (pinfunction "D_3") (pintype "bidirectional"))
      (node (ref "R15") (pin "2") (pinfunction "2_2") (pintype "passive"))
    )
    (net (code "44") (name "Net-(Q2-G)") (class "Default")
      (node (ref "Q2") (pin "3") (pinfunction "G_3") (pintype "passive"))
      (node (ref "R14") (pin "2") (pinfunction "2_2") (pintype "passive"))
      (node (ref "R15") (pin "1") (pinfunction "1_1") (pintype "passive"))
    )
    (net (code "45") (name "Net-(Q3-G1)") (class "Default")
      (node (ref "Q3") (pin "2") (pinfunction "G1_2") (pintype "bidirectional"))
      (node (ref "Q4") (pin "3") (pinfunction "D_3") (pintype "bidirectional"))
      (node (ref "R17") (pin "2") (pinfunction "2_2") (pintype "passive"))
    )
    (net (code "46") (name "Net-(Q3-G2)") (class "Default")
      (node (ref "Q3") (pin "5") (pinfunction "G2_5") (pintype "bidirectional"))
      (node (ref "Q5") (pin "3") (pinfunction "D_3") (pintype "bidirectional"))
      (node (ref "R13") (pin "2") (pinfunction "2_2") (pintype "passive"))
    )
    (net (code "47") (name "OPAMP-OUT") (class "Default")
      (node (ref "IC4") (pin "1") (pinfunction "OUT_1") (pintype "output"))
      (node (ref "R10") (pin "1") (pinfunction "1_1") (pintype "passive"))
      (node (ref "R5") (pin "2") (pinfunction "2_2") (pintype "passive"))
    )
    (net (code "48") (name "P00") (class "Default")
      (node (ref "C17") (pin "1") (pinfunction "P$1_1") (pintype "passive"))
      (node (ref "IC2") (pin "2") (pinfunction "P0.00/XL1_2") (pintype "bidirectional"))
      (node (ref "Y2") (pin "P$2") (pinfunction "2_P$2") (pintype "passive"))
    )
    (net (code "49") (name "P01") (class "Default")
      (node (ref "C18") (pin "1") (pinfunction "P$1_1") (pintype "passive"))
      (node (ref "IC2") (pin "3") (pinfunction "P0.01/XL2_3") (pintype "bidirectional"))
      (node (ref "Y2") (pin "P$1") (pinfunction "1_P$1") (pintype "passive"))
    )
    (net (code "50") (name "P02") (class "Default")
      (node (ref "C27") (pin "1") (pinfunction "P$1_1") (pintype "passive"))
      (node (ref "IC2") (pin "4") (pinfunction "P0.02/AIN0_4") (pintype "bidirectional"))
      (node (ref "JP12") (pin "1") (pinfunction "1_1") (pintype "passive"))
    )
    (net (code "51") (name "P03") (class "Default")
      (node (ref "C28") (pin "1") (pinfunction "P$1_1") (pintype "passive"))
      (node (ref "IC2") (pin "5") (pinfunction "P0.03/AIN1_5") (pintype "bidirectional"))
      (node (ref "JP13") (pin "1") (pinfunction "1_1") (pintype "passive"))
    )
    (net (code "52") (name "P04") (class "Default")
      (node (ref "C29") (pin "1") (pinfunction "P$1_1") (pintype "passive"))
      (node (ref "IC2") (pin "6") (pinfunction "P0.04/AIN2_6") (pintype "bidirectional"))
      (node (ref "JP14") (pin "1") (pinfunction "1_1") (pintype "passive"))
    )
    (net (code "53") (name "P05") (class "Default")
      (node (ref "IC2") (pin "7") (pinfunction "P0.05/AIN3_7") (pintype "bidirectional"))
      (node (ref "UART") (pin "4") (pinfunction "4_4") (pintype "passive"))
    )
    (net (code "54") (name "P06") (class "Default")
      (node (ref "IC2") (pin "8") (pinfunction "P0.06_8") (pintype "bidirectional"))
      (node (ref "UART") (pin "3") (pinfunction "3_3") (pintype "passive"))
    )
    (net (code "55") (name "P07") (class "Default")
      (node (ref "IC2") (pin "9") (pinfunction "P0.07_9") (pintype "bidirectional"))
      (node (ref "UART") (pin "5") (pinfunction "5_5") (pintype "passive"))
    )
    (net (code "56") (name "P08") (class "Default")
      (node (ref "IC2") (pin "10") (pinfunction "P0.08_10") (pintype "bidirectional"))
      (node (ref "UART") (pin "2") (pinfunction "2_2") (pintype "passive"))
    )
    (net (code "57") (name "P09") (class "Default")
      (node (ref "IC2") (pin "11") (pinfunction "P0.09/NFC1_11") (pintype "bidirectional"))
    )
    (net (code "58") (name "P10") (class "Default")
      (node (ref "IC2") (pin "12") (pinfunction "P0.10/NFC2_12") (pintype "bidirectional"))
    )
    (net (code "59") (name "P11") (class "Default")
      (node (ref "IC2") (pin "14") (pinfunction "P0.11_14") (pintype "bidirectional"))
      (node (ref "JP6") (pin "1") (pinfunction "1_1") (pintype "passive"))
    )
    (net (code "60") (name "P12") (class "Default")
      (node (ref "IC2") (pin "15") (pinfunction "P0.12_15") (pintype "bidirectional"))
      (node (ref "JP7") (pin "1") (pinfunction "1_1") (pintype "passive"))
    )
    (net (code "61") (name "P13") (class "Default")
      (node (ref "IC2") (pin "16") (pinfunction "P0.13_16") (pintype "bidirectional"))
      (node (ref "JP8") (pin "1") (pinfunction "1_1") (pintype "passive"))
    )
    (net (code "62") (name "P14") (class "Default")
      (node (ref "IC2") (pin "17") (pinfunction "P0.14_17") (pintype "bidirectional"))
      (node (ref "JP9") (pin "1") (pinfunction "1_1") (pintype "passive"))
    )
    (net (code "63") (name "P16") (class "Default")
      (node (ref "C21") (pin "1") (pinfunction "P$1_1") (pintype "passive"))
      (node (ref "IC2") (pin "19") (pinfunction "P0.16_19") (pintype "bidirectional"))
      (node (ref "R6") (pin "1") (pinfunction "1_1") (pintype "passive"))
      (node (ref "UPDATE") (pin "2") (pinfunction "2_2") (pintype "passive"))
    )
    (net (code "64") (name "P17") (class "Default")
      (node (ref "IC2") (pin "20") (pinfunction "P0.17_20") (pintype "bidirectional"))
      (node (ref "JP10") (pin "1") (pinfunction "1_1") (pintype "passive"))
    )
    (net (code "65") (name "P19") (class "Default")
      (node (ref "C32") (pin "1") (pinfunction "P$1_1") (pintype "passive"))
      (node (ref "IC2") (pin "22") (pinfunction "P0.19_22") (pintype "bidirectional"))
      (node (ref "JP11") (pin "1") (pinfunction "1_1") (pintype "passive"))
    )
    (net (code "66") (name "P23") (class "Default")
      (node (ref "IC2") (pin "28") (pinfunction "P0.23_28") (pintype "bidirectional"))
    )
    (net (code "67") (name "P24") (class "Default")
      (node (ref "IC2") (pin "29") (pinfunction "P0.24_29") (pintype "bidirectional"))
    )
    (net (code "68") (name "P28") (class "Default")
      (node (ref "IC2") (pin "40") (pinfunction "P0.28/AIN4_40") (pintype "bidirectional"))
    )
    (net (code "69") (name "PG") (class "Default")
      (node (ref "JP9") (pin "2") (pinfunction "2_2") (pintype "passive"))
      (node (ref "Q1") (pin "1") (pinfunction "G_1") (pintype "bidirectional"))
    )
    (net (code "70") (name "SCK") (class "Default")
      (node (ref "IC2") (pin "43") (pinfunction "P0.31/AIN7_43") (pintype "bidirectional"))
    )
    (net (code "71") (name "SWDCLK") (class "Default")
      (node (ref "DEBUG1") (pin "4") (pinfunction "SWDCLK/TCK_4") (pintype "bidirectional"))
      (node (ref "IC2") (pin "25") (pinfunction "SWDCLK_25") (pintype "bidirectional"))
      (node (ref "R49") (pin "2") (pinfunction "2_2") (pintype "passive"))
    )
    (net (code "72") (name "SWDIO") (class "Default")
      (node (ref "DEBUG1") (pin "2") (pinfunction "SWDIO/TMS_2") (pintype "bidirectional"))
      (node (ref "IC2") (pin "26") (pinfunction "SWDIO_26") (pintype "bidirectional"))
    )
    (net (code "73") (name "SWO{slash}TDO") (class "Default")
      (node (ref "DEBUG1") (pin "6") (pinfunction "SWO/TDO_6") (pintype "bidirectional"))
      (node (ref "IC2") (pin "21") (pinfunction "P0.18_21") (pintype "bidirectional"))
    )
    (net (code "74") (name "V-ICHG") (class "Default")
      (node (ref "C30") (pin "2") (pinfunction "P$2_2") (pintype "passive"))
      (node (ref "D1") (pin "A") (pinfunction "A_A") (pintype "passive"))
      (node (ref "JP14") (pin "2") (pinfunction "2_2") (pintype "passive"))
      (node (ref "R10") (pin "2") (pinfunction "2_2") (pintype "passive"))
    )
    (net (code "75") (name "V-VCHG") (class "Default")
      (node (ref "C7") (pin "1") (pinfunction "P$1_1") (pintype "passive"))
      (node (ref "D2") (pin "A") (pinfunction "A_A") (pintype "passive"))
      (node (ref "R11") (pin "1") (pinfunction "1_1") (pintype "passive"))
      (node (ref "R12") (pin "1") (pinfunction "1_1") (pintype "passive"))
    )
    (net (code "76") (name "VCHG") (class "Default")
      (node (ref "C4") (pin "+") (pinfunction "+_+") (pintype "passive"))
      (node (ref "JP2") (pin "3") (pinfunction "3_3") (pintype "passive"))
      (node (ref "JP3") (pin "1") (pinfunction "1_1") (pintype "passive"))
      (node (ref "JP4") (pin "1") (pinfunction "1_1") (pintype "passive"))
      (node (ref "Q3") (pin "4") (pinfunction "S2_4") (pintype "bidirectional"))
      (node (ref "R13") (pin "1") (pinfunction "1_1") (pintype "passive"))
    )
    (net (code "77") (name "VDD_BLE") (class "Default")
      (node (ref "C10") (pin "1") (pinfunction "P$1_1") (pintype "passive"))
      (node (ref "C8") (pin "1") (pinfunction "P$1_1") (pintype "passive"))
      (node (ref "C9") (pin "1") (pinfunction "P$1_1") (pintype "passive"))
      (node (ref "DEBUG1") (pin "1") (pinfunction "VCC_1") (pintype "bidirectional"))
      (node (ref "IC2") (pin "13") (pinfunction "VDD_13") (pintype "bidirectional"))
      (node (ref "IC2") (pin "36") (pinfunction "VDD_36") (pintype "bidirectional"))
      (node (ref "IC2") (pin "48") (pinfunction "VDD_48") (pintype "bidirectional"))
      (node (ref "JP13") (pin "2") (pinfunction "2_2") (pintype "passive"))
      (node (ref "JP15") (pin "1") (pinfunction "1_1") (pintype "passive"))
      (node (ref "JP17") (pin "1") (pinfunction "1_1") (pintype "passive"))
      (node (ref "L7") (pin "2") (pinfunction "2_2") (pintype "passive"))
      (node (ref "LS1") (pin "3") (pinfunction "VIN_3") (pintype "input"))
      (node (ref "LS2") (pin "3") (pinfunction "VIN_3") (pintype "input"))
      (node (ref "R6") (pin "2") (pinfunction "2_2") (pintype "passive"))
      (node (ref "R60") (pin "1") (pinfunction "1_1") (pintype "passive"))
    )
    (net (code "78") (name "VDD_MDM") (class "Default")
      (node (ref "JP17") (pin "2") (pinfunction "2_2") (pintype "passive"))
      (node (ref "LS1") (pin "1") (pinfunction "VOUT_1") (pintype "output"))
      (node (ref "UART") (pin "1") (pinfunction "1_1") (pintype "passive"))
    )
    (net (code "79") (name "VDD_SENS") (class "Default")
      (node (ref "JP15") (pin "2") (pinfunction "2_2") (pintype "passive"))
      (node (ref "LS2") (pin "1") (pinfunction "VOUT_1") (pintype "output"))
      (node (ref "SENSOR") (pin "1") (pinfunction "1_1") (pintype "passive"))
    )
    (net (code "80") (name "VDD_WPT") (class "Default")
      (node (ref "C15") (pin "1") (pinfunction "P$1_1") (pintype "passive"))
      (node (ref "D5") (pin "C") (pinfunction "C_C") (pintype "passive"))
      (node (ref "D8") (pin "C") (pinfunction "C_C") (pintype "passive"))
      (node (ref "D9") (pin "C") (pinfunction "C_C") (pintype "passive"))
      (node (ref "Q2") (pin "4") (pinfunction "S_4") (pintype "passive"))
      (node (ref "R14") (pin "1") (pinfunction "1_1") (pintype "passive"))
      (node (ref "R16") (pin "1") (pinfunction "1_1") (pintype "passive"))
      (node (ref "R8") (pin "1") (pinfunction "1_1") (pintype "passive"))
    )
    (net (code "81") (name "VIN") (class "Default")
      (node (ref "C1") (pin "1") (pinfunction "P$1_1") (pintype "passive"))
      (node (ref "IC1") (pin "1") (pinfunction "VIN_1") (pintype "power_in"))
      (node (ref "IC3") (pin "3") (pinfunction "VIN_3") (pintype "input"))
      (node (ref "Q2") (pin "1") (pinfunction "D_1") (pintype "passive"))
      (node (ref "Q2") (pin "2") (pinfunction "D_2") (pintype "passive"))
      (node (ref "Q2") (pin "5") (pinfunction "D_5") (pintype "passive"))
      (node (ref "Q2") (pin "6") (pinfunction "D_6") (pintype "passive"))
    )
    (net (code "82") (name "VMEAS") (class "Default")
      (node (ref "D3") (pin "C") (pinfunction "C_C") (pintype "passive"))
      (node (ref "JP2") (pin "1") (pinfunction "1_1") (pintype "passive"))
      (node (ref "Q3") (pin "1") (pinfunction "S1_1") (pintype "bidirectional"))
      (node (ref "R11") (pin "2") (pinfunction "2_2") (pintype "passive"))
      (node (ref "R17") (pin "1") (pinfunction "1_1") (pintype "passive"))
    )
    (net (code "83") (name "WAKE-UP") (class "Default")
      (node (ref "D4") (pin "C") (pinfunction "C_C") (pintype "passive"))
      (node (ref "JP11") (pin "2") (pinfunction "2_2") (pintype "passive"))
      (node (ref "R16") (pin "2") (pinfunction "2_2") (pintype "passive"))
    )
    (net (code "84") (name "unconnected-(DEBUG1-KEY-Pad7)") (class "Default")
      (node (ref "DEBUG1") (pin "7") (pinfunction "KEY_7") (pintype "bidirectional"))
    )
    (net (code "85") (name "unconnected-(DEBUG1-NC{slash}TDI-Pad8)") (class "Default")
      (node (ref "DEBUG1") (pin "8") (pinfunction "NC/TDI_8") (pintype "bidirectional"))
    )
    (net (code "86") (name "unconnected-(IC2-NC-Pad44)") (class "Default")
      (node (ref "IC2") (pin "44") (pinfunction "NC_44") (pintype "bidirectional"))
    )
    (net (code "87") (name "~{RESET}") (class "Default")
      (node (ref "C22") (pin "1") (pinfunction "P$1_1") (pintype "passive"))
      (node (ref "DEBUG1") (pin "10") (pinfunction "~{RESET}_10") (pintype "bidirectional"))
      (node (ref "IC2") (pin "24") (pinfunction "P0.21/RESET_24") (pintype "bidirectional"))
      (node (ref "R60") (pin "2") (pinfunction "2_2") (pintype "passive"))
    )
  )
)
